# Housekeeping.net
KiCad netlist of a schematic drawn in Altium Designer
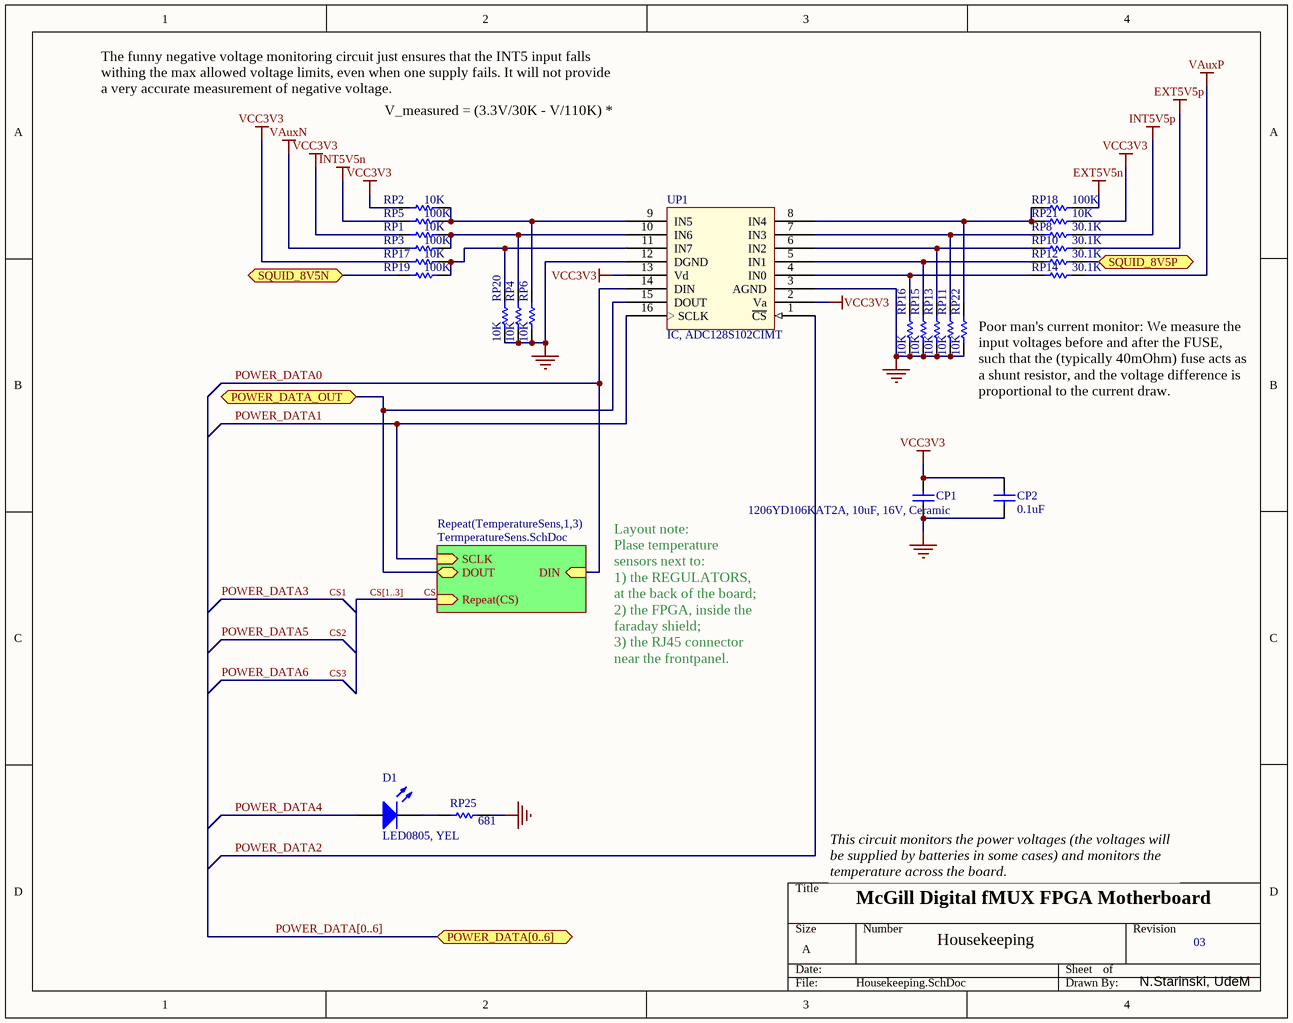
[diagram p0: Housekeeping.SchDoc]

(export (version "E")
  (design (tool "Eeschema 10.0.6"))
  (components
    (comp (ref "CP1")
      (value "1206YD106KAT2A, 10uF, 16V, Ceramic")
      (footprint "CC3225-1210")
      (description "CAP POL 1206YD106KAT2A")
      (fields (field (name "PUBLISHER") "Altium Limited"))
      (libsource (lib "Miscellaneous Devices") (part "Cap Semi"))
    )
    (comp (ref "CP2")
      (value "0.1uF")
      (footprint "CC1608-0603")
      (description "Capacitor (Semiconductor SIM Model)")
      (fields (field (name "PUBLISHER") "Altium Limited"))
      (libsource (lib "Miscellaneous Devices") (part "Cap Semi"))
    )
    (comp (ref "D1")
      (value "LED0805, YEL")
      (footprint "SMD _LED")
      (description "LED 0805 LTST-C170YKT")
      (fields (field (name "PUBLISHER") "Altium Limited"))
      (libsource (lib "Miscellaneous Devices") (part "LED3"))
    )
    (comp (ref "RP1")
      (value "10K")
      (footprint "CR1608-0603")
      (description "Resistor 0603")
      (fields (field (name "PUBLISHER") "Altium Limited"))
      (libsource (lib "Miscellaneous Devices") (part "Res Semi"))
    )
    (comp (ref "RP2")
      (value "10K")
      (footprint "CR1608-0603")
      (description "Resistor 0603")
      (fields (field (name "PUBLISHER") "Altium Limited"))
      (libsource (lib "Miscellaneous Devices") (part "Res Semi"))
    )
    (comp (ref "RP3")
      (value "100K")
      (footprint "CR1608-0603")
      (description "Semiconductor Resistor")
      (fields (field (name "PUBLISHER") "Altium Limited"))
      (libsource (lib "Miscellaneous Devices") (part "Res Semi"))
    )
    (comp (ref "RP4")
      (value "10K")
      (footprint "CR1608-0603")
      (description "Resistor 0603")
      (fields (field (name "PUBLISHER") "Altium Limited"))
      (libsource (lib "Miscellaneous Devices") (part "Res Semi"))
    )
    (comp (ref "RP5")
      (value "100K")
      (footprint "CR1608-0603")
      (description "Semiconductor Resistor")
      (fields (field (name "PUBLISHER") "Altium Limited"))
      (libsource (lib "Miscellaneous Devices") (part "Res Semi"))
    )
    (comp (ref "RP6")
      (value "10K")
      (footprint "CR1608-0603")
      (description "Resistor 0603")
      (fields (field (name "PUBLISHER") "Altium Limited"))
      (libsource (lib "Miscellaneous Devices") (part "Res Semi"))
    )
    (comp (ref "RP8")
      (value "30.1K")
      (footprint "CR1608-0603")
      (description "Resistor 0603")
      (fields (field (name "PUBLISHER") "Altium Limited"))
      (libsource (lib "Miscellaneous Devices") (part "Res Semi"))
    )
    (comp (ref "RP10")
      (value "30.1K")
      (footprint "CR1608-0603")
      (description "Resistor 0603")
      (fields (field (name "PUBLISHER") "Altium Limited"))
      (libsource (lib "Miscellaneous Devices") (part "Res Semi"))
    )
    (comp (ref "RP11")
      (value "10K")
      (footprint "CR1608-0603")
      (description "Resistor 0603")
      (fields (field (name "PUBLISHER") "Altium Limited"))
      (libsource (lib "Miscellaneous Devices") (part "Res Semi"))
    )
    (comp (ref "RP12")
      (value "30.1K")
      (footprint "CR1608-0603")
      (description "Resistor 0603")
      (fields (field (name "PUBLISHER") "Altium Limited"))
      (libsource (lib "Miscellaneous Devices") (part "Res Semi"))
    )
    (comp (ref "RP13")
      (value "10K")
      (footprint "CR1608-0603")
      (description "Resistor 0603")
      (fields (field (name "PUBLISHER") "Altium Limited"))
      (libsource (lib "Miscellaneous Devices") (part "Res Semi"))
    )
    (comp (ref "RP14")
      (value "30.1K")
      (footprint "CR1608-0603")
      (description "Resistor 0603")
      (fields (field (name "PUBLISHER") "Altium Limited"))
      (libsource (lib "Miscellaneous Devices") (part "Res Semi"))
    )
    (comp (ref "RP15")
      (value "10K")
      (footprint "CR1608-0603")
      (description "Resistor 0603")
      (fields (field (name "PUBLISHER") "Altium Limited"))
      (libsource (lib "Miscellaneous Devices") (part "Res Semi"))
    )
    (comp (ref "RP16")
      (value "10K")
      (footprint "CR1608-0603")
      (description "Resistor 0603")
      (fields (field (name "PUBLISHER") "Altium Limited"))
      (libsource (lib "Miscellaneous Devices") (part "Res Semi"))
    )
    (comp (ref "RP17")
      (value "10K")
      (footprint "CR1608-0603")
      (description "Resistor 0603")
      (fields (field (name "PUBLISHER") "Altium Limited"))
      (libsource (lib "Miscellaneous Devices") (part "Res Semi"))
    )
    (comp (ref "RP18")
      (value "100K")
      (footprint "CR1608-0603")
      (description "Semiconductor Resistor")
      (fields (field (name "PUBLISHER") "Altium Limited"))
      (libsource (lib "Miscellaneous Devices") (part "Res Semi"))
    )
    (comp (ref "RP19")
      (value "100K")
      (footprint "CR1608-0603")
      (description "Semiconductor Resistor")
      (fields (field (name "PUBLISHER") "Altium Limited"))
      (libsource (lib "Miscellaneous Devices") (part "Res Semi"))
    )
    (comp (ref "RP20")
      (value "10K")
      (footprint "CR1608-0603")
      (description "Resistor 0603")
      (fields (field (name "PUBLISHER") "Altium Limited"))
      (libsource (lib "Miscellaneous Devices") (part "Res Semi"))
    )
    (comp (ref "RP21")
      (value "10K")
      (footprint "CR1608-0603")
      (description "Resistor 0603")
      (fields (field (name "PUBLISHER") "Altium Limited"))
      (libsource (lib "Miscellaneous Devices") (part "Res Semi"))
    )
    (comp (ref "RP22")
      (value "10K")
      (footprint "CR1608-0603")
      (description "Resistor 0603")
      (fields (field (name "PUBLISHER") "Altium Limited"))
      (libsource (lib "Miscellaneous Devices") (part "Res Semi"))
    )
    (comp (ref "RP25")
      (value "681")
      (footprint "CR1608-0603")
      (description "Resistor 0603")
      (fields (field (name "PUBLISHER") "Altium Limited"))
      (libsource (lib "Miscellaneous Devices") (part "Res Semi"))
    )
    (comp (ref "UP1")
      (value "IC, ADC128S102CIMT")
      (footprint "SSO-G16/X.45")
      (description "8-Channels, 500kSPS to 1 MSPS, 12-Bit ADC")
      (libsource (lib "NSC Converter Analog to Digital") (part "ADC128S102"))
    )
  )
  (nets
    (net (code "6") (name "/POWER_DATA0") (class "Default")
      (node (ref "UP1") (pin "14") (pinfunction "DIN_14") (pintype "passive"))
    )
    (net (code "7") (name "/POWER_DATA1") (class "Default")
      (node (ref "UP1") (pin "16") (pinfunction "SCLK_16") (pintype "passive"))
    )
    (net (code "8") (name "/POWER_DATA2") (class "Default")
      (node (ref "UP1") (pin "1") (pinfunction "~{CS}_1") (pintype "input"))
    )
    (net (code "9") (name "/POWER_DATA4") (class "Default")
      (node (ref "D1") (pin "1") (pinfunction "A_1") (pintype "passive"))
    )
    (net (code "11") (name "/POWER_DATA_OUT") (class "Default")
      (node (ref "UP1") (pin "15") (pinfunction "DOUT_15") (pintype "passive"))
    )
    (net (code "12") (name "/SQUID_8V5N") (class "Default")
      (node (ref "RP19") (pin "1") (pinfunction "1_1") (pintype "passive"))
    )
    (net (code "13") (name "/SQUID_8V5P") (class "Default")
      (node (ref "RP12") (pin "2") (pinfunction "2_2") (pintype "passive"))
    )
    (net (code "14") (name "EXT5V5n") (class "Default")
      (node (ref "RP18") (pin "2") (pinfunction "2_2") (pintype "passive"))
    )
    (net (code "15") (name "EXT5V5p") (class "Default")
      (node (ref "RP10") (pin "2") (pinfunction "2_2") (pintype "passive"))
    )
    (net (code "16") (name "GND") (class "Default")
      (node (ref "CP1") (pin "1") (pinfunction "1_1") (pintype "passive"))
      (node (ref "CP2") (pin "1") (pinfunction "1_1") (pintype "passive"))
      (node (ref "RP11") (pin "1") (pinfunction "1_1") (pintype "passive"))
      (node (ref "RP13") (pin "1") (pinfunction "1_1") (pintype "passive"))
      (node (ref "RP15") (pin "1") (pinfunction "1_1") (pintype "passive"))
      (node (ref "RP16") (pin "1") (pinfunction "1_1") (pintype "passive"))
      (node (ref "RP20") (pin "1") (pinfunction "1_1") (pintype "passive"))
      (node (ref "RP22") (pin "1") (pinfunction "1_1") (pintype "passive"))
      (node (ref "RP25") (pin "2") (pinfunction "2_2") (pintype "passive"))
      (node (ref "RP4") (pin "1") (pinfunction "1_1") (pintype "passive"))
      (node (ref "RP6") (pin "1") (pinfunction "1_1") (pintype "passive"))
      (node (ref "UP1") (pin "12") (pinfunction "DGND_12") (pintype "power_in"))
      (node (ref "UP1") (pin "3") (pinfunction "AGND_3") (pintype "power_in"))
    )
    (net (code "17") (name "INT5V5n") (class "Default")
      (node (ref "RP5") (pin "1") (pinfunction "1_1") (pintype "passive"))
    )
    (net (code "18") (name "INT5V5p") (class "Default")
      (node (ref "RP8") (pin "2") (pinfunction "2_2") (pintype "passive"))
    )
    (net (code "19") (name "Net-(D1-K)") (class "Default")
      (node (ref "D1") (pin "2") (pinfunction "K_2") (pintype "passive"))
      (node (ref "RP25") (pin "1") (pinfunction "1_1") (pintype "passive"))
    )
    (net (code "20") (name "Net-(UP1-IN0)") (class "Default")
      (node (ref "RP14") (pin "1") (pinfunction "1_1") (pintype "passive"))
      (node (ref "RP16") (pin "2") (pinfunction "2_2") (pintype "passive"))
      (node (ref "UP1") (pin "4") (pinfunction "IN0_4") (pintype "passive"))
    )
    (net (code "21") (name "Net-(UP1-IN1)") (class "Default")
      (node (ref "RP12") (pin "1") (pinfunction "1_1") (pintype "passive"))
      (node (ref "RP15") (pin "2") (pinfunction "2_2") (pintype "passive"))
      (node (ref "UP1") (pin "5") (pinfunction "IN1_5") (pintype "passive"))
    )
    (net (code "22") (name "Net-(UP1-IN2)") (class "Default")
      (node (ref "RP10") (pin "1") (pinfunction "1_1") (pintype "passive"))
      (node (ref "RP13") (pin "2") (pinfunction "2_2") (pintype "passive"))
      (node (ref "UP1") (pin "6") (pinfunction "IN2_6") (pintype "passive"))
    )
    (net (code "23") (name "Net-(UP1-IN3)") (class "Default")
      (node (ref "RP11") (pin "2") (pinfunction "2_2") (pintype "passive"))
      (node (ref "RP8") (pin "1") (pinfunction "1_1") (pintype "passive"))
      (node (ref "UP1") (pin "7") (pinfunction "IN3_7") (pintype "passive"))
    )
    (net (code "24") (name "Net-(UP1-IN4)") (class "Default")
      (node (ref "RP18") (pin "1") (pinfunction "1_1") (pintype "passive"))
      (node (ref "RP21") (pin "1") (pinfunction "1_1") (pintype "passive"))
      (node (ref "RP22") (pin "2") (pinfunction "2_2") (pintype "passive"))
      (node (ref "UP1") (pin "8") (pinfunction "IN4_8") (pintype "passive"))
    )
    (net (code "25") (name "Net-(UP1-IN5)") (class "Default")
      (node (ref "RP2") (pin "2") (pinfunction "2_2") (pintype "passive"))
      (node (ref "RP5") (pin "2") (pinfunction "2_2") (pintype "passive"))
      (node (ref "RP6") (pin "2") (pinfunction "2_2") (pintype "passive"))
      (node (ref "UP1") (pin "9") (pinfunction "IN5_9") (pintype "passive"))
    )
    (net (code "26") (name "Net-(UP1-IN6)") (class "Default")
      (node (ref "RP1") (pin "2") (pinfunction "2_2") (pintype "passive"))
      (node (ref "RP3") (pin "2") (pinfunction "2_2") (pintype "passive"))
      (node (ref "RP4") (pin "2") (pinfunction "2_2") (pintype "passive"))
      (node (ref "UP1") (pin "10") (pinfunction "IN6_10") (pintype "passive"))
    )
    (net (code "27") (name "Net-(UP1-IN7)") (class "Default")
      (node (ref "RP17") (pin "2") (pinfunction "2_2") (pintype "passive"))
      (node (ref "RP19") (pin "2") (pinfunction "2_2") (pintype "passive"))
      (node (ref "RP20") (pin "2") (pinfunction "2_2") (pintype "passive"))
      (node (ref "UP1") (pin "11") (pinfunction "IN7_11") (pintype "passive"))
    )
    (net (code "28") (name "VAuxN") (class "Default")
      (node (ref "RP3") (pin "1") (pinfunction "1_1") (pintype "passive"))
    )
    (net (code "29") (name "VAuxP") (class "Default")
      (node (ref "RP14") (pin "2") (pinfunction "2_2") (pintype "passive"))
    )
    (net (code "30") (name "VCC3V3") (class "Default")
      (node (ref "CP1") (pin "2") (pinfunction "2_2") (pintype "passive"))
      (node (ref "CP2") (pin "2") (pinfunction "2_2") (pintype "passive"))
      (node (ref "RP1") (pin "1") (pinfunction "1_1") (pintype "passive"))
      (node (ref "RP17") (pin "1") (pinfunction "1_1") (pintype "passive"))
      (node (ref "RP2") (pin "1") (pinfunction "1_1") (pintype "passive"))
      (node (ref "RP21") (pin "2") (pinfunction "2_2") (pintype "passive"))
      (node (ref "UP1") (pin "13") (pinfunction "Vd_13") (pintype "power_in"))
      (node (ref "UP1") (pin "2") (pinfunction "Va_2") (pintype "power_in"))
    )
  )
)
